# PCB-TCH-MENU2.net
KiCad netlist of a schematic drawn in EAGLE
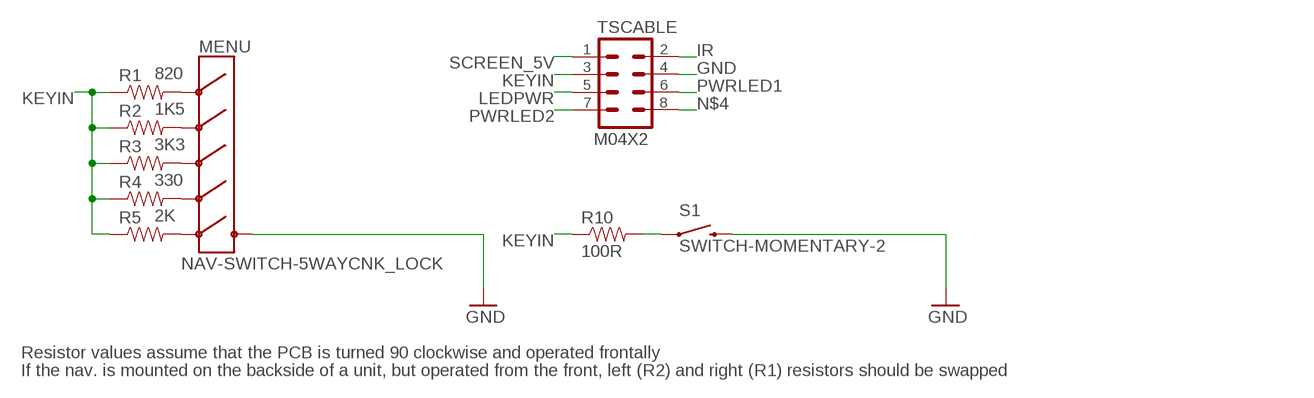
[diagram p0: schematic, sheet 1]

(export (version "E")
  (design (tool "Eeschema 10.0.6"))
  (components
    (comp (ref "MENU")
      (value "NAV-SWITCH-5WAYCNK_LOCK")
      (footprint "eagle-import:NAV-SWITCH-5WAY")
      (libsource (lib "eagle-import") (part "NAV-SWITCH-5WAYCNK_LOCK"))
    )
    (comp (ref "R1")
      (value "820")
      (footprint "eagle-import:0603-RES")
      (libsource (lib "eagle-import") (part "RESISTOR0603-RES"))
    )
    (comp (ref "R2")
      (value "1K5")
      (footprint "eagle-import:0603-RES")
      (libsource (lib "eagle-import") (part "RESISTOR0603-RES"))
    )
    (comp (ref "R3")
      (value "3K3")
      (footprint "eagle-import:0603-RES")
      (libsource (lib "eagle-import") (part "RESISTOR0603-RES"))
    )
    (comp (ref "R4")
      (value "330")
      (footprint "eagle-import:0603-RES")
      (libsource (lib "eagle-import") (part "RESISTOR0603-RES"))
    )
    (comp (ref "R5")
      (value "2K")
      (footprint "eagle-import:0603-RES")
      (libsource (lib "eagle-import") (part "RESISTOR0603-RES"))
    )
    (comp (ref "R10")
      (value "100R")
      (footprint "eagle-import:0603-RES")
      (libsource (lib "eagle-import") (part "RESISTOR0603-RES"))
    )
    (comp (ref "S1")
      (value "SWITCH-MOMENTARY-2")
      (footprint "eagle-import:TACTILE_SWITCH_TALL")
      (libsource (lib "eagle-import") (part "SWITCH-MOMENTARY-2"))
    )
    (comp (ref "TSCABLE")
      (value "M04X2")
      (footprint "eagle-import:2X4")
      (libsource (lib "eagle-import") (part "M04X2"))
    )
  )
  (nets
    (net (code "1") (name "/IR") (class "Default")
      (node (ref "TSCABLE") (pin "2") (pinfunction "2_2") (pintype "passive"))
    )
    (net (code "2") (name "/KEYIN") (class "Default")
      (node (ref "R1") (pin "1") (pinfunction "1_1") (pintype "passive"))
      (node (ref "R10") (pin "1") (pinfunction "1_1") (pintype "passive"))
      (node (ref "R2") (pin "1") (pinfunction "1_1") (pintype "passive"))
      (node (ref "R3") (pin "1") (pinfunction "1_1") (pintype "passive"))
      (node (ref "R4") (pin "1") (pinfunction "1_1") (pintype "passive"))
      (node (ref "R5") (pin "1") (pinfunction "1_1") (pintype "passive"))
      (node (ref "TSCABLE") (pin "3") (pinfunction "3_3") (pintype "passive"))
    )
    (net (code "3") (name "/LEDPWR") (class "Default")
      (node (ref "TSCABLE") (pin "5") (pinfunction "5_5") (pintype "passive"))
    )
    (net (code "4") (name "/N$4") (class "Default")
      (node (ref "TSCABLE") (pin "8") (pinfunction "8_8") (pintype "passive"))
    )
    (net (code "5") (name "/PWRLED1") (class "Default")
      (node (ref "TSCABLE") (pin "6") (pinfunction "6_6") (pintype "passive"))
    )
    (net (code "6") (name "/PWRLED2") (class "Default")
      (node (ref "TSCABLE") (pin "7") (pinfunction "7_7") (pintype "passive"))
    )
    (net (code "7") (name "/SCREEN_5V") (class "Default")
      (node (ref "TSCABLE") (pin "1") (pinfunction "1_1") (pintype "passive"))
    )
    (net (code "8") (name "GND") (class "Default")
      (node (ref "MENU") (pin "PIN4") (pinfunction "COMMON_PIN4") (pintype "bidirectional"))
      (node (ref "S1") (pin "B2") (pinfunction "2_B2") (pintype "passive"))
      (node (ref "TSCABLE") (pin "4") (pinfunction "4_4") (pintype "passive"))
    )
    (net (code "9") (name "Net-(MENU-DWN)") (class "Default")
      (node (ref "MENU") (pin "PIN3") (pinfunction "DWN_PIN3") (pintype "bidirectional"))
      (node (ref "R2") (pin "2") (pinfunction "2_2") (pintype "passive"))
    )
    (net (code "10") (name "Net-(MENU-LEFT)") (class "Default")
      (node (ref "MENU") (pin "PIN2") (pinfunction "LEFT_PIN2") (pintype "bidirectional"))
      (node (ref "R3") (pin "2") (pinfunction "2_2") (pintype "passive"))
    )
    (net (code "11") (name "Net-(MENU-PUSH)") (class "Default")
      (node (ref "MENU") (pin "PIN6") (pinfunction "PUSH_PIN6") (pintype "bidirectional"))
      (node (ref "R5") (pin "2") (pinfunction "2_2") (pintype "passive"))
    )
    (net (code "12") (name "Net-(MENU-RIGHT)") (class "Default")
      (node (ref "MENU") (pin "PIN5") (pinfunction "RIGHT_PIN5") (pintype "bidirectional"))
      (node (ref "R4") (pin "2") (pinfunction "2_2") (pintype "passive"))
    )
    (net (code "13") (name "Net-(MENU-UP)") (class "Default")
      (node (ref "MENU") (pin "PIN1") (pinfunction "UP_PIN1") (pintype "bidirectional"))
      (node (ref "R1") (pin "2") (pinfunction "2_2") (pintype "passive"))
    )
    (net (code "14") (name "Net-(S1-1)") (class "Default")
      (node (ref "R10") (pin "2") (pinfunction "2_2") (pintype "passive"))
      (node (ref "S1") (pin "A2") (pinfunction "1_A2") (pintype "passive"))
    )
  )
)
